# Voeding.net
KiCad netlist of a schematic drawn in Altium Designer
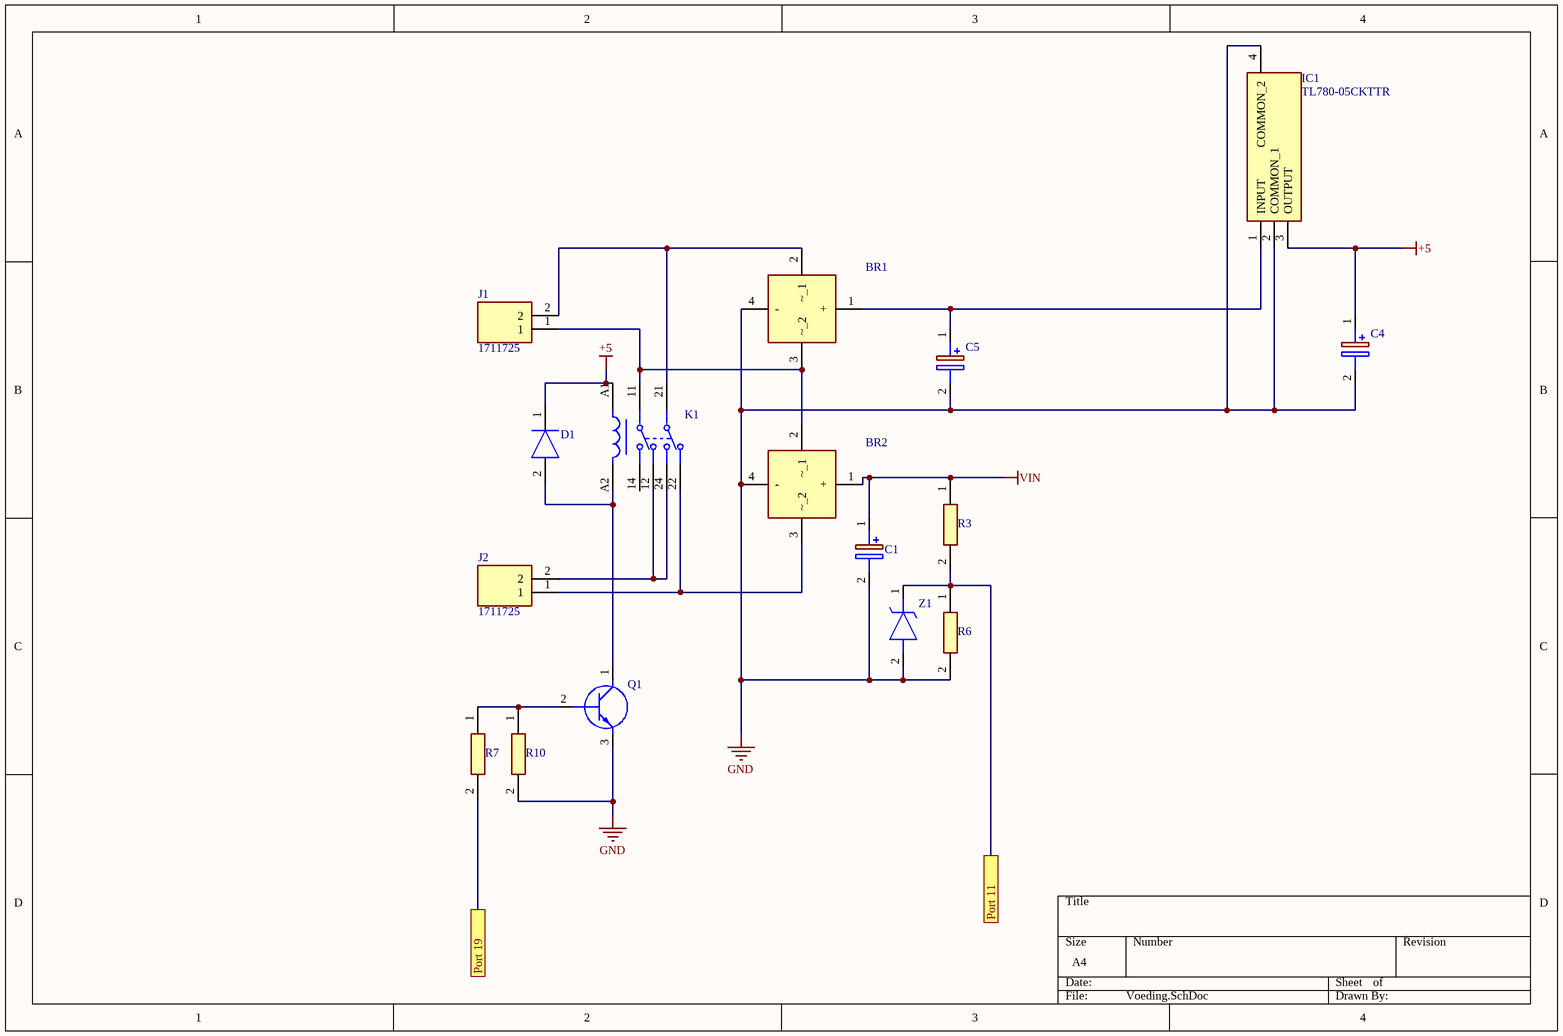
[diagram p0: Voeding.SchDoc]

(export (version "E")
  (design (tool "Eeschema 10.0.6"))
  (components
    (comp (ref "BR1")
      (value "GBU6J-E3_45")
      (footprint "Bridge rectifier")
      (description "Bridge Rectifier")
      (fields (field (name "MANUFACTURER_PART_NUMBER") "GBU6J-E3/45"))
      (libsource (lib "Schlib1") (part "GBU6J-E3_45"))
    )
    (comp (ref "BR2")
      (value "GBU6J-E3_45")
      (footprint "Bridge rectifier")
      (description "Bridge Rectifier")
      (fields (field (name "MANUFACTURER_PART_NUMBER") "GBU6J-E3/45"))
      (libsource (lib "Schlib1") (part "GBU6J-E3_45"))
    )
    (comp (ref "C1")
      (value "ESK478M050AQ3AA")
      (footprint "4700µF 50V")
      (description "Capacitor Polarised 50V 4700uF")
      (fields (field (name "MOUSER2 PART NUMBER") "80-ESK478M050AQ3AA"))
      (libsource (lib "Schlib1") (part "ESK478M050AQ3AA"))
    )
    (comp (ref "C4")
      (value "EEU-FR1H100")
      (footprint "10µF 50V")
      (description "Capacitor Polarised 50VDC 10uF")
      (fields (field (name "MOUSER2 PART NUMBER") "667-EEU-FR1H100"))
      (libsource (lib "Schlib1") (part "EEU-FR1H100"))
    )
    (comp (ref "C5")
      (value "EEU-FR1H100")
      (footprint "100µF")
      (description "Capacitor Polarised 50VDC 10uF")
      (fields (field (name "MOUSER2 PART NUMBER") "667-EEU-FR1H100"))
      (libsource (lib "Schlib1") (part "EEU-FR1H100"))
    )
    (comp (ref "D1")
      (value "1N4007G-T")
      (footprint "D1")
      (description "Diode")
      (fields (field (name "MOUSER2 PART NUMBER") "621-1N4007G-T"))
      (libsource (lib "Schlib1") (part "1N4007G-T"))
    )
    (comp (ref "IC1")
      (value "TL780-05CKTTR")
      (footprint "IC1")
      (description "Integrated Circuit")
      (libsource (lib "Schlib1") (part "TL780-05CKTTR"))
    )
    (comp (ref "J1")
      (value "1711725")
      (footprint "Phoenix")
      (description "Connector")
      (libsource (lib "Schlib1") (part "1711725"))
    )
    (comp (ref "J2")
      (value "1711725")
      (footprint "Phoenix")
      (description "Connector")
      (libsource (lib "Schlib1") (part "1711725"))
    )
    (comp (ref "K1")
      (value "RT424615")
      (footprint "FP-RT424615-MFG")
      (description "RELAY GEN PURPOSE DPDT 8A 115V")
      (libsource (lib "Schlib1") (part "CMP-03395-000241-1"))
    )
    (comp (ref "Q1")
      (value "BC547CBU")
      (footprint "TTTT")
      (description "Transistor BJT NPN")
      (libsource (lib "Schlib1") (part "BC547CBU"))
    )
    (comp (ref "R3")
      (value "CRCW080510K0DHEAP")
      (footprint "Resistor")
      (description "Resistor 68KOhm")
      (libsource (lib "Schlib1") (part "CRCW080510K0DHEAP"))
    )
    (comp (ref "R6")
      (value "CRCW080510K0DHEAP")
      (footprint "Resistor")
      (description "Resistor 10KOhm")
      (libsource (lib "Schlib1") (part "CRCW080510K0DHEAP"))
    )
    (comp (ref "R7")
      (value "CRCW080510K0DHEAP")
      (footprint "Resistor")
      (description "Resistor 10KOhm")
      (libsource (lib "Schlib1") (part "CRCW080510K0DHEAP"))
    )
    (comp (ref "R10")
      (value "CRCW08054K70FKEAHP")
      (footprint "Resistor")
      (description "Resistor 4.7KOhm")
      (fields (field (name "MOUSER2 PART NUMBER") "71-CRCW08054K70FKEAH"))
      (libsource (lib "Schlib1") (part "CRCW08054K70FKEAHP"))
    )
    (comp (ref "Z1")
      (value "SZMMSZ5231BT1G")
      (footprint "Zener")
      (description "Zener Diode")
      (fields (field (name "MOUSER2 PART NUMBER") "863-SZMMSZ5231BT1G"))
      (libsource (lib "Schlib1") (part "SZMMSZ5231BT1G"))
    )
  )
  (nets
    (net (code "1") (name "+5") (class "Default")
      (node (ref "C4") (pin "1") (pinfunction "+_1") (pintype "power_in"))
      (node (ref "D1") (pin "1") (pinfunction "K_1") (pintype "passive"))
      (node (ref "IC1") (pin "3") (pinfunction "OUTPUT_3") (pintype "passive"))
      (node (ref "K1") (pin "A1") (pinfunction "A1_A1") (pintype "passive"))
    )
    (net (code "2") (name "/Port 11") (class "Default")
      (node (ref "R3") (pin "2") (pinfunction "2_2") (pintype "passive"))
      (node (ref "R6") (pin "1") (pinfunction "1_1") (pintype "passive"))
      (node (ref "Z1") (pin "1") (pinfunction "K_1") (pintype "passive"))
    )
    (net (code "3") (name "/Port 19") (class "Default")
      (node (ref "R7") (pin "2") (pinfunction "2_2") (pintype "passive"))
    )
    (net (code "4") (name "GND") (class "Default")
      (node (ref "BR1") (pin "4") (pinfunction "-_4") (pintype "passive"))
      (node (ref "BR2") (pin "4") (pinfunction "-_4") (pintype "passive"))
      (node (ref "C1") (pin "2") (pinfunction "-_2") (pintype "passive"))
      (node (ref "C4") (pin "2") (pinfunction "-_2") (pintype "power_in"))
      (node (ref "C5") (pin "2") (pinfunction "-_2") (pintype "power_in"))
      (node (ref "IC1") (pin "2") (pinfunction "COMMON_1_2") (pintype "passive"))
      (node (ref "IC1") (pin "4") (pinfunction "COMMON_2_4") (pintype "passive"))
      (node (ref "Q1") (pin "3") (pinfunction "E_3") (pintype "passive"))
      (node (ref "R10") (pin "2") (pinfunction "2_2") (pintype "passive"))
      (node (ref "R6") (pin "2") (pinfunction "2_2") (pintype "passive"))
      (node (ref "Z1") (pin "2") (pinfunction "A_2") (pintype "passive"))
    )
    (net (code "5") (name "Net-(BR1-+)") (class "Default")
      (node (ref "BR1") (pin "1") (pinfunction "+_1") (pintype "passive"))
      (node (ref "C5") (pin "1") (pinfunction "+_1") (pintype "power_in"))
      (node (ref "IC1") (pin "1") (pinfunction "INPUT_1") (pintype "passive"))
    )
    (net (code "6") (name "Net-(BR1-~_1)") (class "Default")
      (node (ref "BR1") (pin "2") (pinfunction "~_1_2") (pintype "passive"))
      (node (ref "J1") (pin "2") (pinfunction "2_2") (pintype "passive"))
      (node (ref "K1") (pin "21") (pinfunction "21_21") (pintype "passive"))
    )
    (net (code "7") (name "Net-(BR1-~_2)") (class "Default")
      (node (ref "BR1") (pin "3") (pinfunction "~_2_3") (pintype "passive"))
      (node (ref "BR2") (pin "2") (pinfunction "~_1_2") (pintype "passive"))
      (node (ref "J1") (pin "1") (pinfunction "1_1") (pintype "passive"))
      (node (ref "K1") (pin "11") (pinfunction "11_11") (pintype "passive"))
    )
    (net (code "8") (name "Net-(BR2-~_2)") (class "Default")
      (node (ref "BR2") (pin "3") (pinfunction "~_2_3") (pintype "passive"))
      (node (ref "J2") (pin "1") (pinfunction "1_1") (pintype "passive"))
      (node (ref "K1") (pin "22") (pinfunction "22_22") (pintype "passive"))
    )
    (net (code "9") (name "Net-(D1-A)") (class "Default")
      (node (ref "D1") (pin "2") (pinfunction "A_2") (pintype "passive"))
      (node (ref "K1") (pin "A2") (pinfunction "A2_A2") (pintype "passive"))
      (node (ref "Q1") (pin "1") (pinfunction "C_1") (pintype "passive"))
    )
    (net (code "10") (name "Net-(J2-Pad2)") (class "Default")
      (node (ref "J2") (pin "2") (pinfunction "2_2") (pintype "passive"))
      (node (ref "K1") (pin "12") (pinfunction "12_12") (pintype "passive"))
      (node (ref "K1") (pin "24") (pinfunction "24_24") (pintype "passive"))
    )
    (net (code "11") (name "Net-(Q1-B)") (class "Default")
      (node (ref "Q1") (pin "2") (pinfunction "B_2") (pintype "passive"))
      (node (ref "R10") (pin "1") (pinfunction "1_1") (pintype "passive"))
      (node (ref "R7") (pin "1") (pinfunction "1_1") (pintype "passive"))
    )
    (net (code "12") (name "VIN") (class "Default")
      (node (ref "BR2") (pin "1") (pinfunction "+_1") (pintype "passive"))
      (node (ref "C1") (pin "1") (pinfunction "+_1") (pintype "passive"))
      (node (ref "R3") (pin "1") (pinfunction "1_1") (pintype "passive"))
    )
    (net (code "13") (name "unconnected-(K1-Pad14)") (class "Default")
      (node (ref "K1") (pin "14") (pinfunction "14_14") (pintype "passive"))
    )
  )
)
